# ShootingBoard.net
KiCad netlist of a schematic drawn in EAGLE
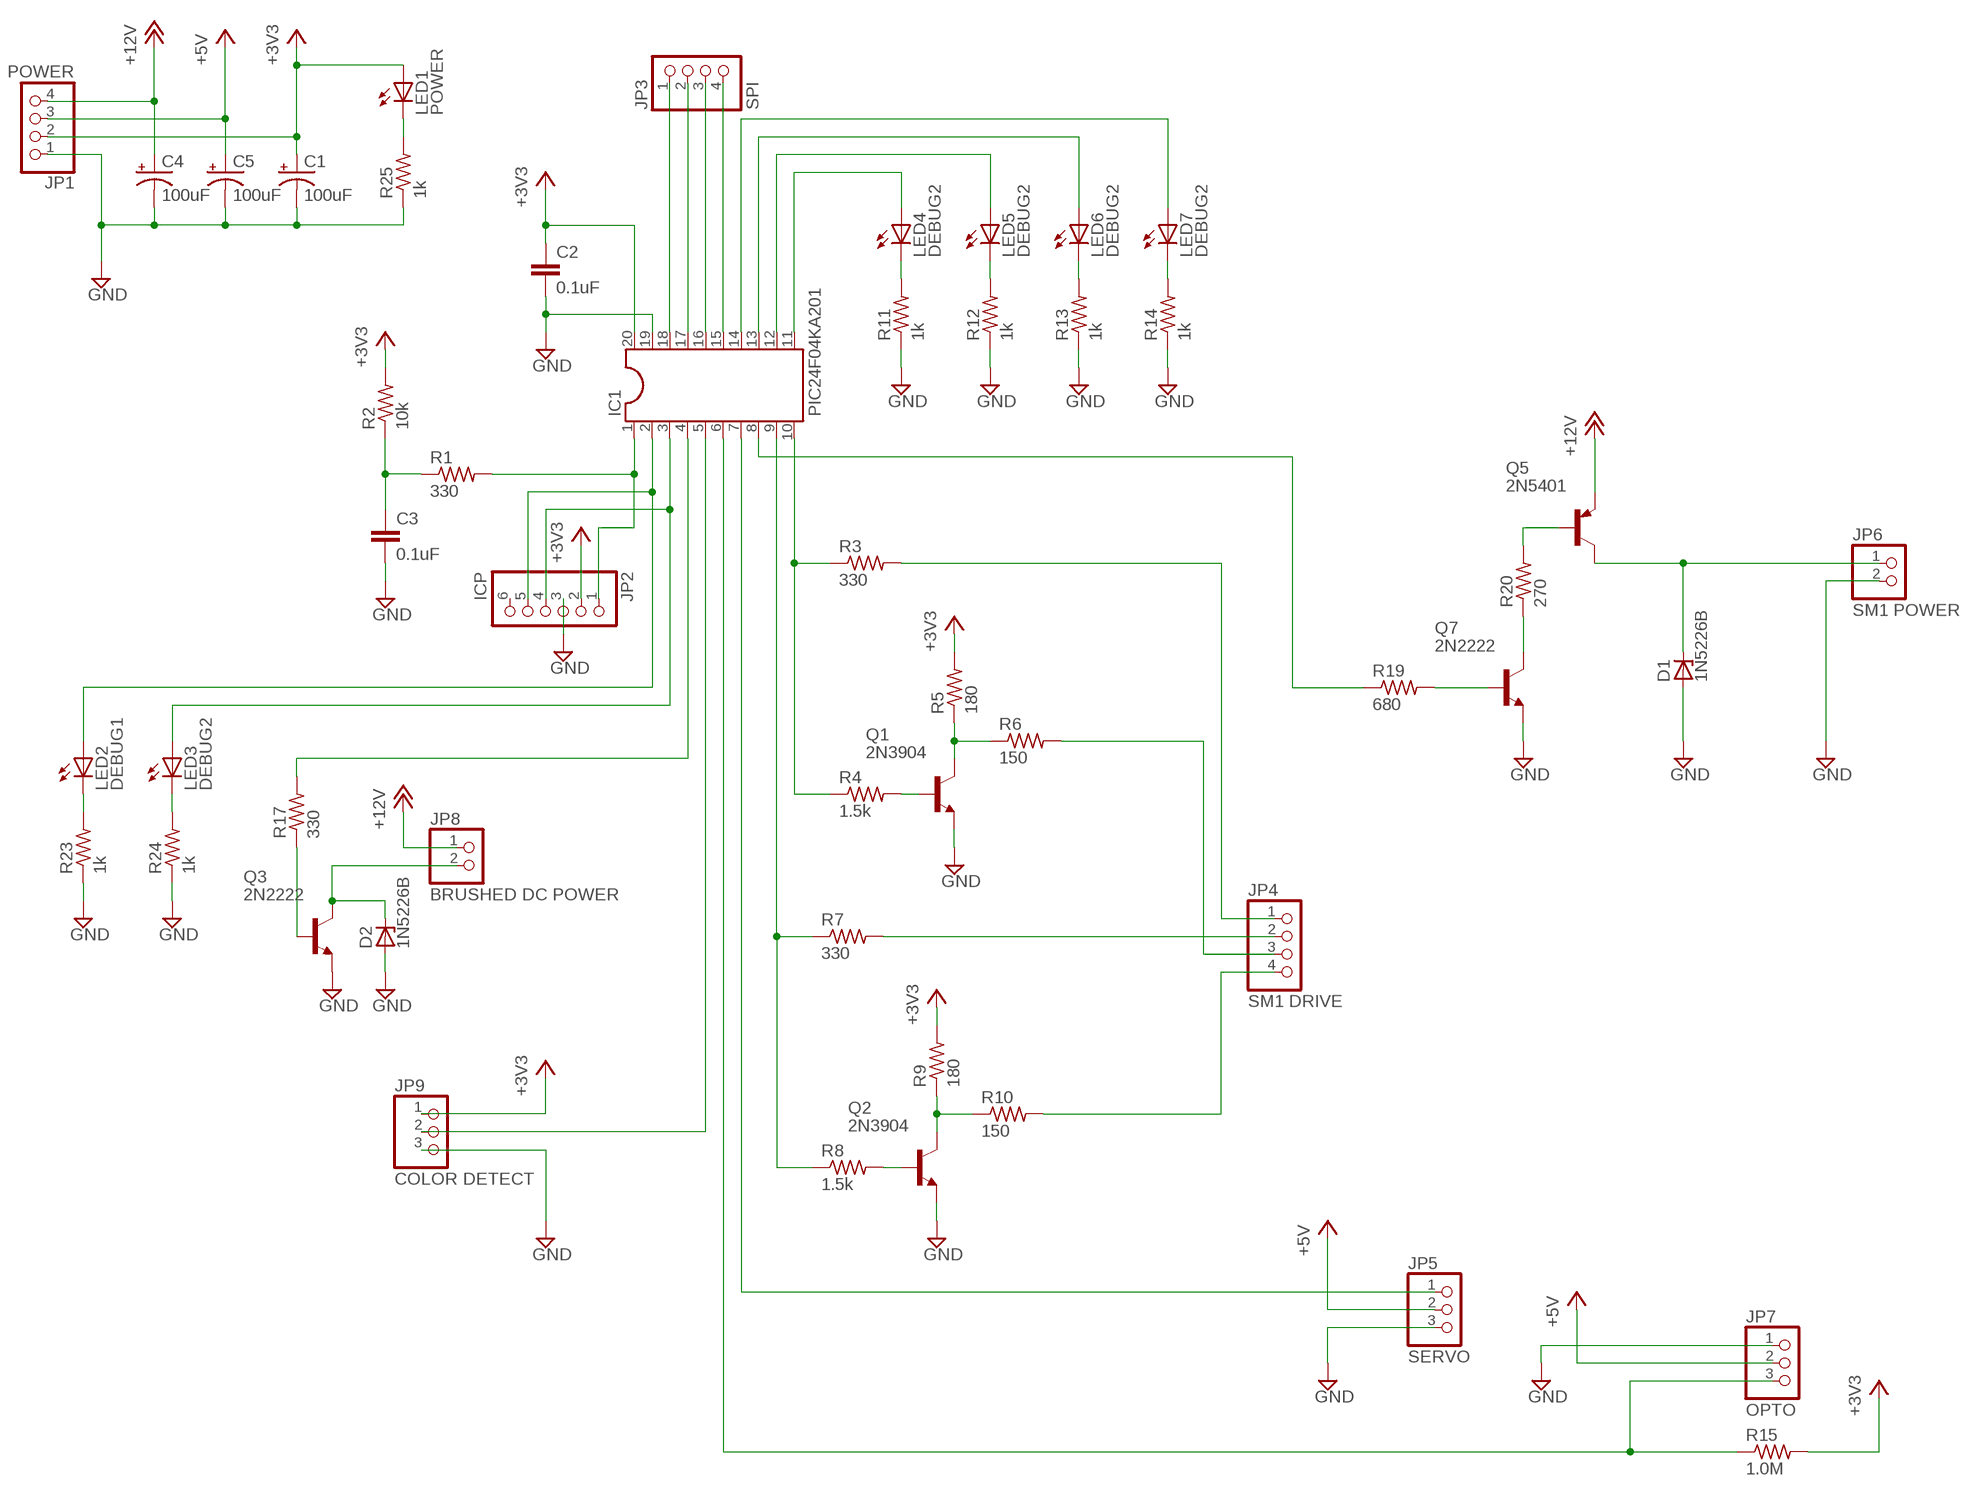
[diagram p0: schematic, sheet 1]

(export (version "E")
  (design (tool "Eeschema 10.0.6"))
  (components
    (comp (ref "C1")
      (value "100uF")
      (footprint "eagle-import:E2,5-7")
      (libsource (lib "eagle-import") (part "CPOL-USE2.5-7"))
    )
    (comp (ref "C2")
      (value "0.1uF")
      (footprint "eagle-import:C0805")
      (libsource (lib "eagle-import") (part "C-EUC0805"))
    )
    (comp (ref "C3")
      (value "0.1uF")
      (footprint "eagle-import:C0805")
      (libsource (lib "eagle-import") (part "C-EUC0805"))
    )
    (comp (ref "C4")
      (value "100uF")
      (footprint "eagle-import:E2,5-7")
      (libsource (lib "eagle-import") (part "CPOL-USE2.5-7"))
    )
    (comp (ref "C5")
      (value "100uF")
      (footprint "eagle-import:E2,5-7")
      (libsource (lib "eagle-import") (part "CPOL-USE2.5-7"))
    )
    (comp (ref "D1")
      (value "1N5226B")
      (footprint "eagle-import:DO35Z10")
      (libsource (lib "eagle-import") (part "ZPD"))
    )
    (comp (ref "D2")
      (value "1N5226B")
      (footprint "eagle-import:DO35Z10")
      (libsource (lib "eagle-import") (part "ZPD"))
    )
    (comp (ref "IC1")
      (value "PIC24F04KA201")
      (footprint "eagle-import:SOCKET-20")
      (libsource (lib "eagle-import") (part "DIL20S"))
    )
    (comp (ref "JP1")
      (value "POWER")
      (footprint "eagle-import:1X04")
      (libsource (lib "eagle-import") (part "PINHD-1X4"))
    )
    (comp (ref "JP2")
      (value "ICP")
      (footprint "eagle-import:1X06")
      (libsource (lib "eagle-import") (part "PINHD-1X6"))
    )
    (comp (ref "JP3")
      (value "SPI")
      (footprint "eagle-import:1X04")
      (libsource (lib "eagle-import") (part "PINHD-1X4"))
    )
    (comp (ref "JP4")
      (value "SM1 DRIVE")
      (footprint "eagle-import:1X04")
      (libsource (lib "eagle-import") (part "PINHD-1X4"))
    )
    (comp (ref "JP5")
      (value "SERVO")
      (footprint "eagle-import:1X03")
      (libsource (lib "eagle-import") (part "PINHD-1X3"))
    )
    (comp (ref "JP6")
      (value "SM1 POWER")
      (footprint "eagle-import:1X02")
      (libsource (lib "eagle-import") (part "PINHD-1X2"))
    )
    (comp (ref "JP7")
      (value "OPTO")
      (footprint "eagle-import:1X03")
      (libsource (lib "eagle-import") (part "PINHD-1X3"))
    )
    (comp (ref "JP8")
      (value "BRUSHED DC POWER")
      (footprint "eagle-import:1X02")
      (libsource (lib "eagle-import") (part "PINHD-1X2"))
    )
    (comp (ref "JP9")
      (value "COLOR DETECT")
      (footprint "eagle-import:1X03")
      (libsource (lib "eagle-import") (part "PINHD-1X3"))
    )
    (comp (ref "LED1")
      (value "POWER")
      (footprint "eagle-import:LED3MM")
      (libsource (lib "eagle-import") (part "LED3MM"))
    )
    (comp (ref "LED2")
      (value "DEBUG1")
      (footprint "eagle-import:LED3MM")
      (libsource (lib "eagle-import") (part "LED3MM"))
    )
    (comp (ref "LED3")
      (value "DEBUG2")
      (footprint "eagle-import:LED3MM")
      (libsource (lib "eagle-import") (part "LED3MM"))
    )
    (comp (ref "LED4")
      (value "DEBUG2")
      (footprint "eagle-import:LED3MM")
      (libsource (lib "eagle-import") (part "LED3MM"))
    )
    (comp (ref "LED5")
      (value "DEBUG2")
      (footprint "eagle-import:LED3MM")
      (libsource (lib "eagle-import") (part "LED3MM"))
    )
    (comp (ref "LED6")
      (value "DEBUG2")
      (footprint "eagle-import:LED3MM")
      (libsource (lib "eagle-import") (part "LED3MM"))
    )
    (comp (ref "LED7")
      (value "DEBUG2")
      (footprint "eagle-import:LED3MM")
      (libsource (lib "eagle-import") (part "LED3MM"))
    )
    (comp (ref "Q1")
      (value "2N3904")
      (footprint "eagle-import:TO92")
      (libsource (lib "eagle-import") (part "2N3904"))
    )
    (comp (ref "Q2")
      (value "2N3904")
      (footprint "eagle-import:TO92")
      (libsource (lib "eagle-import") (part "2N3904"))
    )
    (comp (ref "Q3")
      (value "2N2222")
      (footprint "eagle-import:TO92")
      (libsource (lib "eagle-import") (part "2N3904"))
    )
    (comp (ref "Q5")
      (value "2N5401")
      (footprint "eagle-import:TO92")
      (libsource (lib "eagle-import") (part "2N3906"))
    )
    (comp (ref "Q7")
      (value "2N2222")
      (footprint "eagle-import:TO92")
      (libsource (lib "eagle-import") (part "2N3904"))
    )
    (comp (ref "R1")
      (value "330")
      (footprint "eagle-import:R0805")
      (libsource (lib "eagle-import") (part "R-US_R0805"))
    )
    (comp (ref "R2")
      (value "10k")
      (footprint "eagle-import:R0805")
      (libsource (lib "eagle-import") (part "R-US_R0805"))
    )
    (comp (ref "R3")
      (value "330")
      (footprint "eagle-import:R0805")
      (libsource (lib "eagle-import") (part "R-US_R0805"))
    )
    (comp (ref "R4")
      (value "1.5k")
      (footprint "eagle-import:R0805")
      (libsource (lib "eagle-import") (part "R-US_R0805"))
    )
    (comp (ref "R5")
      (value "180")
      (footprint "eagle-import:R0805")
      (libsource (lib "eagle-import") (part "R-US_R0805"))
    )
    (comp (ref "R6")
      (value "150")
      (footprint "eagle-import:R0805")
      (libsource (lib "eagle-import") (part "R-US_R0805"))
    )
    (comp (ref "R7")
      (value "330")
      (footprint "eagle-import:R0805")
      (libsource (lib "eagle-import") (part "R-US_R0805"))
    )
    (comp (ref "R8")
      (value "1.5k")
      (footprint "eagle-import:R0805")
      (libsource (lib "eagle-import") (part "R-US_R0805"))
    )
    (comp (ref "R9")
      (value "180")
      (footprint "eagle-import:R0805")
      (libsource (lib "eagle-import") (part "R-US_R0805"))
    )
    (comp (ref "R10")
      (value "150")
      (footprint "eagle-import:R0805")
      (libsource (lib "eagle-import") (part "R-US_R0805"))
    )
    (comp (ref "R11")
      (value "1k")
      (footprint "eagle-import:R0805")
      (libsource (lib "eagle-import") (part "R-US_R0805"))
    )
    (comp (ref "R12")
      (value "1k")
      (footprint "eagle-import:R0805")
      (libsource (lib "eagle-import") (part "R-US_R0805"))
    )
    (comp (ref "R13")
      (value "1k")
      (footprint "eagle-import:R0805")
      (libsource (lib "eagle-import") (part "R-US_R0805"))
    )
    (comp (ref "R14")
      (value "1k")
      (footprint "eagle-import:R0805")
      (libsource (lib "eagle-import") (part "R-US_R0805"))
    )
    (comp (ref "R15")
      (value "1.0M")
      (footprint "eagle-import:R0805")
      (libsource (lib "eagle-import") (part "R-US_R0805"))
    )
    (comp (ref "R17")
      (value "330")
      (footprint "eagle-import:R0805")
      (libsource (lib "eagle-import") (part "R-US_R0805"))
    )
    (comp (ref "R19")
      (value "680")
      (footprint "eagle-import:R0805")
      (libsource (lib "eagle-import") (part "R-US_R0805"))
    )
    (comp (ref "R20")
      (value "270")
      (footprint "eagle-import:R0805")
      (libsource (lib "eagle-import") (part "R-US_R0805"))
    )
    (comp (ref "R23")
      (value "1k")
      (footprint "eagle-import:R0805")
      (libsource (lib "eagle-import") (part "R-US_R0805"))
    )
    (comp (ref "R24")
      (value "1k")
      (footprint "eagle-import:R0805")
      (libsource (lib "eagle-import") (part "R-US_R0805"))
    )
    (comp (ref "R25")
      (value "1k")
      (footprint "eagle-import:R0805")
      (libsource (lib "eagle-import") (part "R-US_R0805"))
    )
  )
  (nets
    (net (code "1") (name "+3V3") (class "Default")
      (node (ref "C1") (pin "+") (pinfunction "+_+") (pintype "passive"))
      (node (ref "C2") (pin "1") (pinfunction "1_1") (pintype "passive"))
      (node (ref "IC1") (pin "20") (pinfunction "20_20") (pintype "passive"))
      (node (ref "JP1") (pin "2") (pinfunction "2_2") (pintype "passive"))
      (node (ref "JP2") (pin "2") (pinfunction "2_2") (pintype "passive"))
      (node (ref "JP9") (pin "1") (pinfunction "1_1") (pintype "passive"))
      (node (ref "LED1") (pin "A") (pinfunction "A_A") (pintype "passive"))
      (node (ref "R15") (pin "2") (pinfunction "2_2") (pintype "passive"))
      (node (ref "R2") (pin "2") (pinfunction "2_2") (pintype "passive"))
      (node (ref "R5") (pin "2") (pinfunction "2_2") (pintype "passive"))
      (node (ref "R9") (pin "2") (pinfunction "2_2") (pintype "passive"))
    )
    (net (code "2") (name "+5V") (class "Default")
      (node (ref "C5") (pin "+") (pinfunction "+_+") (pintype "passive"))
      (node (ref "JP1") (pin "3") (pinfunction "3_3") (pintype "passive"))
      (node (ref "JP5") (pin "2") (pinfunction "2_2") (pintype "passive"))
      (node (ref "JP7") (pin "2") (pinfunction "2_2") (pintype "passive"))
    )
    (net (code "3") (name "+12V") (class "Default")
      (node (ref "C4") (pin "+") (pinfunction "+_+") (pintype "passive"))
      (node (ref "JP1") (pin "4") (pinfunction "4_4") (pintype "passive"))
      (node (ref "JP8") (pin "1") (pinfunction "1_1") (pintype "passive"))
      (node (ref "Q5") (pin "3") (pinfunction "E_3") (pintype "passive"))
    )
    (net (code "4") (name "GND") (class "Default")
      (node (ref "C1") (pin "-") (pinfunction "-_-") (pintype "passive"))
      (node (ref "C2") (pin "2") (pinfunction "2_2") (pintype "passive"))
      (node (ref "C3") (pin "2") (pinfunction "2_2") (pintype "passive"))
      (node (ref "C4") (pin "-") (pinfunction "-_-") (pintype "passive"))
      (node (ref "C5") (pin "-") (pinfunction "-_-") (pintype "passive"))
      (node (ref "D1") (pin "A") (pinfunction "A_A") (pintype "passive"))
      (node (ref "D2") (pin "A") (pinfunction "A_A") (pintype "passive"))
      (node (ref "IC1") (pin "19") (pinfunction "19_19") (pintype "passive"))
      (node (ref "JP1") (pin "1") (pinfunction "1_1") (pintype "passive"))
      (node (ref "JP2") (pin "3") (pinfunction "3_3") (pintype "passive"))
      (node (ref "JP5") (pin "3") (pinfunction "3_3") (pintype "passive"))
      (node (ref "JP6") (pin "2") (pinfunction "2_2") (pintype "passive"))
      (node (ref "JP7") (pin "1") (pinfunction "1_1") (pintype "passive"))
      (node (ref "JP9") (pin "3") (pinfunction "3_3") (pintype "passive"))
      (node (ref "Q1") (pin "3") (pinfunction "E_3") (pintype "passive"))
      (node (ref "Q2") (pin "3") (pinfunction "E_3") (pintype "passive"))
      (node (ref "Q3") (pin "3") (pinfunction "E_3") (pintype "passive"))
      (node (ref "Q7") (pin "3") (pinfunction "E_3") (pintype "passive"))
      (node (ref "R11") (pin "1") (pinfunction "1_1") (pintype "passive"))
      (node (ref "R12") (pin "1") (pinfunction "1_1") (pintype "passive"))
      (node (ref "R13") (pin "1") (pinfunction "1_1") (pintype "passive"))
      (node (ref "R14") (pin "1") (pinfunction "1_1") (pintype "passive"))
      (node (ref "R23") (pin "1") (pinfunction "1_1") (pintype "passive"))
      (node (ref "R24") (pin "1") (pinfunction "1_1") (pintype "passive"))
      (node (ref "R25") (pin "1") (pinfunction "1_1") (pintype "passive"))
    )
    (net (code "5") (name "Net-(C3-Pad1)") (class "Default")
      (node (ref "C3") (pin "1") (pinfunction "1_1") (pintype "passive"))
      (node (ref "R1") (pin "1") (pinfunction "1_1") (pintype "passive"))
      (node (ref "R2") (pin "1") (pinfunction "1_1") (pintype "passive"))
    )
    (net (code "6") (name "Net-(IC1-Pad1)") (class "Default")
      (node (ref "IC1") (pin "1") (pinfunction "1_1") (pintype "passive"))
      (node (ref "JP2") (pin "1") (pinfunction "1_1") (pintype "passive"))
      (node (ref "R1") (pin "2") (pinfunction "2_2") (pintype "passive"))
    )
    (net (code "7") (name "Net-(IC1-Pad2)") (class "Default")
      (node (ref "IC1") (pin "2") (pinfunction "2_2") (pintype "passive"))
      (node (ref "JP2") (pin "5") (pinfunction "5_5") (pintype "passive"))
      (node (ref "LED2") (pin "A") (pinfunction "A_A") (pintype "passive"))
    )
    (net (code "8") (name "Net-(IC1-Pad3)") (class "Default")
      (node (ref "IC1") (pin "3") (pinfunction "3_3") (pintype "passive"))
      (node (ref "JP2") (pin "4") (pinfunction "4_4") (pintype "passive"))
      (node (ref "LED3") (pin "A") (pinfunction "A_A") (pintype "passive"))
    )
    (net (code "9") (name "Net-(IC1-Pad4)") (class "Default")
      (node (ref "IC1") (pin "4") (pinfunction "4_4") (pintype "passive"))
      (node (ref "R17") (pin "2") (pinfunction "2_2") (pintype "passive"))
    )
    (net (code "10") (name "Net-(IC1-Pad5)") (class "Default")
      (node (ref "IC1") (pin "5") (pinfunction "5_5") (pintype "passive"))
      (node (ref "JP9") (pin "2") (pinfunction "2_2") (pintype "passive"))
    )
    (net (code "11") (name "Net-(IC1-Pad6)") (class "Default")
      (node (ref "IC1") (pin "6") (pinfunction "6_6") (pintype "passive"))
      (node (ref "JP7") (pin "3") (pinfunction "3_3") (pintype "passive"))
      (node (ref "R15") (pin "1") (pinfunction "1_1") (pintype "passive"))
    )
    (net (code "12") (name "Net-(IC1-Pad7)") (class "Default")
      (node (ref "IC1") (pin "7") (pinfunction "7_7") (pintype "passive"))
      (node (ref "JP5") (pin "1") (pinfunction "1_1") (pintype "passive"))
    )
    (net (code "13") (name "Net-(IC1-Pad8)") (class "Default")
      (node (ref "IC1") (pin "8") (pinfunction "8_8") (pintype "passive"))
      (node (ref "R19") (pin "1") (pinfunction "1_1") (pintype "passive"))
    )
    (net (code "14") (name "Net-(IC1-Pad9)") (class "Default")
      (node (ref "IC1") (pin "9") (pinfunction "9_9") (pintype "passive"))
      (node (ref "R7") (pin "1") (pinfunction "1_1") (pintype "passive"))
      (node (ref "R8") (pin "1") (pinfunction "1_1") (pintype "passive"))
    )
    (net (code "15") (name "Net-(IC1-Pad10)") (class "Default")
      (node (ref "IC1") (pin "10") (pinfunction "10_10") (pintype "passive"))
      (node (ref "R3") (pin "1") (pinfunction "1_1") (pintype "passive"))
      (node (ref "R4") (pin "1") (pinfunction "1_1") (pintype "passive"))
    )
    (net (code "16") (name "Net-(IC1-Pad11)") (class "Default")
      (node (ref "IC1") (pin "11") (pinfunction "11_11") (pintype "passive"))
      (node (ref "LED4") (pin "A") (pinfunction "A_A") (pintype "passive"))
    )
    (net (code "17") (name "Net-(IC1-Pad12)") (class "Default")
      (node (ref "IC1") (pin "12") (pinfunction "12_12") (pintype "passive"))
      (node (ref "LED5") (pin "A") (pinfunction "A_A") (pintype "passive"))
    )
    (net (code "18") (name "Net-(IC1-Pad13)") (class "Default")
      (node (ref "IC1") (pin "13") (pinfunction "13_13") (pintype "passive"))
      (node (ref "LED6") (pin "A") (pinfunction "A_A") (pintype "passive"))
    )
    (net (code "19") (name "Net-(IC1-Pad14)") (class "Default")
      (node (ref "IC1") (pin "14") (pinfunction "14_14") (pintype "passive"))
      (node (ref "LED7") (pin "A") (pinfunction "A_A") (pintype "passive"))
    )
    (net (code "20") (name "Net-(IC1-Pad15)") (class "Default")
      (node (ref "IC1") (pin "15") (pinfunction "15_15") (pintype "passive"))
      (node (ref "JP3") (pin "4") (pinfunction "4_4") (pintype "passive"))
    )
    (net (code "21") (name "Net-(IC1-Pad16)") (class "Default")
      (node (ref "IC1") (pin "16") (pinfunction "16_16") (pintype "passive"))
      (node (ref "JP3") (pin "3") (pinfunction "3_3") (pintype "passive"))
    )
    (net (code "22") (name "Net-(IC1-Pad17)") (class "Default")
      (node (ref "IC1") (pin "17") (pinfunction "17_17") (pintype "passive"))
      (node (ref "JP3") (pin "2") (pinfunction "2_2") (pintype "passive"))
    )
    (net (code "23") (name "Net-(IC1-Pad18)") (class "Default")
      (node (ref "IC1") (pin "18") (pinfunction "18_18") (pintype "passive"))
      (node (ref "JP3") (pin "1") (pinfunction "1_1") (pintype "passive"))
    )
    (net (code "24") (name "Net-(JP4-Pad1)") (class "Default")
      (node (ref "JP4") (pin "1") (pinfunction "1_1") (pintype "passive"))
      (node (ref "R3") (pin "2") (pinfunction "2_2") (pintype "passive"))
    )
    (net (code "25") (name "Net-(JP4-Pad2)") (class "Default")
      (node (ref "JP4") (pin "2") (pinfunction "2_2") (pintype "passive"))
      (node (ref "R7") (pin "2") (pinfunction "2_2") (pintype "passive"))
    )
    (net (code "26") (name "Net-(JP4-Pad3)") (class "Default")
      (node (ref "JP4") (pin "3") (pinfunction "3_3") (pintype "passive"))
      (node (ref "R6") (pin "2") (pinfunction "2_2") (pintype "passive"))
    )
    (net (code "27") (name "Net-(JP4-Pad4)") (class "Default")
      (node (ref "JP4") (pin "4") (pinfunction "4_4") (pintype "passive"))
      (node (ref "R10") (pin "2") (pinfunction "2_2") (pintype "passive"))
    )
    (net (code "28") (name "Net-(LED1-C)") (class "Default")
      (node (ref "LED1") (pin "K") (pinfunction "C_K") (pintype "passive"))
      (node (ref "R25") (pin "2") (pinfunction "2_2") (pintype "passive"))
    )
    (net (code "29") (name "Net-(LED2-C)") (class "Default")
      (node (ref "LED2") (pin "K") (pinfunction "C_K") (pintype "passive"))
      (node (ref "R23") (pin "2") (pinfunction "2_2") (pintype "passive"))
    )
    (net (code "30") (name "Net-(LED3-C)") (class "Default")
      (node (ref "LED3") (pin "K") (pinfunction "C_K") (pintype "passive"))
      (node (ref "R24") (pin "2") (pinfunction "2_2") (pintype "passive"))
    )
    (net (code "31") (name "Net-(LED4-C)") (class "Default")
      (node (ref "LED4") (pin "K") (pinfunction "C_K") (pintype "passive"))
      (node (ref "R11") (pin "2") (pinfunction "2_2") (pintype "passive"))
    )
    (net (code "32") (name "Net-(LED5-C)") (class "Default")
      (node (ref "LED5") (pin "K") (pinfunction "C_K") (pintype "passive"))
      (node (ref "R12") (pin "2") (pinfunction "2_2") (pintype "passive"))
    )
    (net (code "33") (name "Net-(LED6-C)") (class "Default")
      (node (ref "LED6") (pin "K") (pinfunction "C_K") (pintype "passive"))
      (node (ref "R13") (pin "2") (pinfunction "2_2") (pintype "passive"))
    )
    (net (code "34") (name "Net-(LED7-C)") (class "Default")
      (node (ref "LED7") (pin "K") (pinfunction "C_K") (pintype "passive"))
      (node (ref "R14") (pin "2") (pinfunction "2_2") (pintype "passive"))
    )
    (net (code "35") (name "Net-(Q1-B)") (class "Default")
      (node (ref "Q1") (pin "2") (pinfunction "B_2") (pintype "passive"))
      (node (ref "R4") (pin "2") (pinfunction "2_2") (pintype "passive"))
    )
    (net (code "36") (name "Net-(Q1-C)") (class "Default")
      (node (ref "Q1") (pin "1") (pinfunction "C_1") (pintype "passive"))
      (node (ref "R5") (pin "1") (pinfunction "1_1") (pintype "passive"))
      (node (ref "R6") (pin "1") (pinfunction "1_1") (pintype "passive"))
    )
    (net (code "37") (name "Net-(Q2-B)") (class "Default")
      (node (ref "Q2") (pin "2") (pinfunction "B_2") (pintype "passive"))
      (node (ref "R8") (pin "2") (pinfunction "2_2") (pintype "passive"))
    )
    (net (code "38") (name "Net-(Q2-C)") (class "Default")
      (node (ref "Q2") (pin "1") (pinfunction "C_1") (pintype "passive"))
      (node (ref "R10") (pin "1") (pinfunction "1_1") (pintype "passive"))
      (node (ref "R9") (pin "1") (pinfunction "1_1") (pintype "passive"))
    )
    (net (code "39") (name "Net-(Q3-B)") (class "Default")
      (node (ref "Q3") (pin "2") (pinfunction "B_2") (pintype "passive"))
      (node (ref "R17") (pin "1") (pinfunction "1_1") (pintype "passive"))
    )
    (net (code "40") (name "Net-(Q3-C)") (class "Default")
      (node (ref "D2") (pin "C") (pinfunction "C_C") (pintype "passive"))
      (node (ref "JP8") (pin "2") (pinfunction "2_2") (pintype "passive"))
      (node (ref "Q3") (pin "1") (pinfunction "C_1") (pintype "passive"))
    )
    (net (code "41") (name "Net-(Q5-B)") (class "Default")
      (node (ref "Q5") (pin "2") (pinfunction "B_2") (pintype "passive"))
      (node (ref "R20") (pin "2") (pinfunction "2_2") (pintype "passive"))
    )
    (net (code "42") (name "Net-(Q5-C)") (class "Default")
      (node (ref "D1") (pin "C") (pinfunction "C_C") (pintype "passive"))
      (node (ref "JP6") (pin "1") (pinfunction "1_1") (pintype "passive"))
      (node (ref "Q5") (pin "1") (pinfunction "C_1") (pintype "passive"))
    )
    (net (code "43") (name "Net-(Q7-B)") (class "Default")
      (node (ref "Q7") (pin "2") (pinfunction "B_2") (pintype "passive"))
      (node (ref "R19") (pin "2") (pinfunction "2_2") (pintype "passive"))
    )
    (net (code "44") (name "Net-(Q7-C)") (class "Default")
      (node (ref "Q7") (pin "1") (pinfunction "C_1") (pintype "passive"))
      (node (ref "R20") (pin "1") (pinfunction "1_1") (pintype "passive"))
    )
    (net (code "45") (name "unconnected-(JP2-Pad6)") (class "Default")
      (node (ref "JP2") (pin "6") (pinfunction "6_6") (pintype "passive"))
    )
  )
)
